# MC70_FSK_Modboard.net
KiCad netlist of a schematic drawn in EAGLE
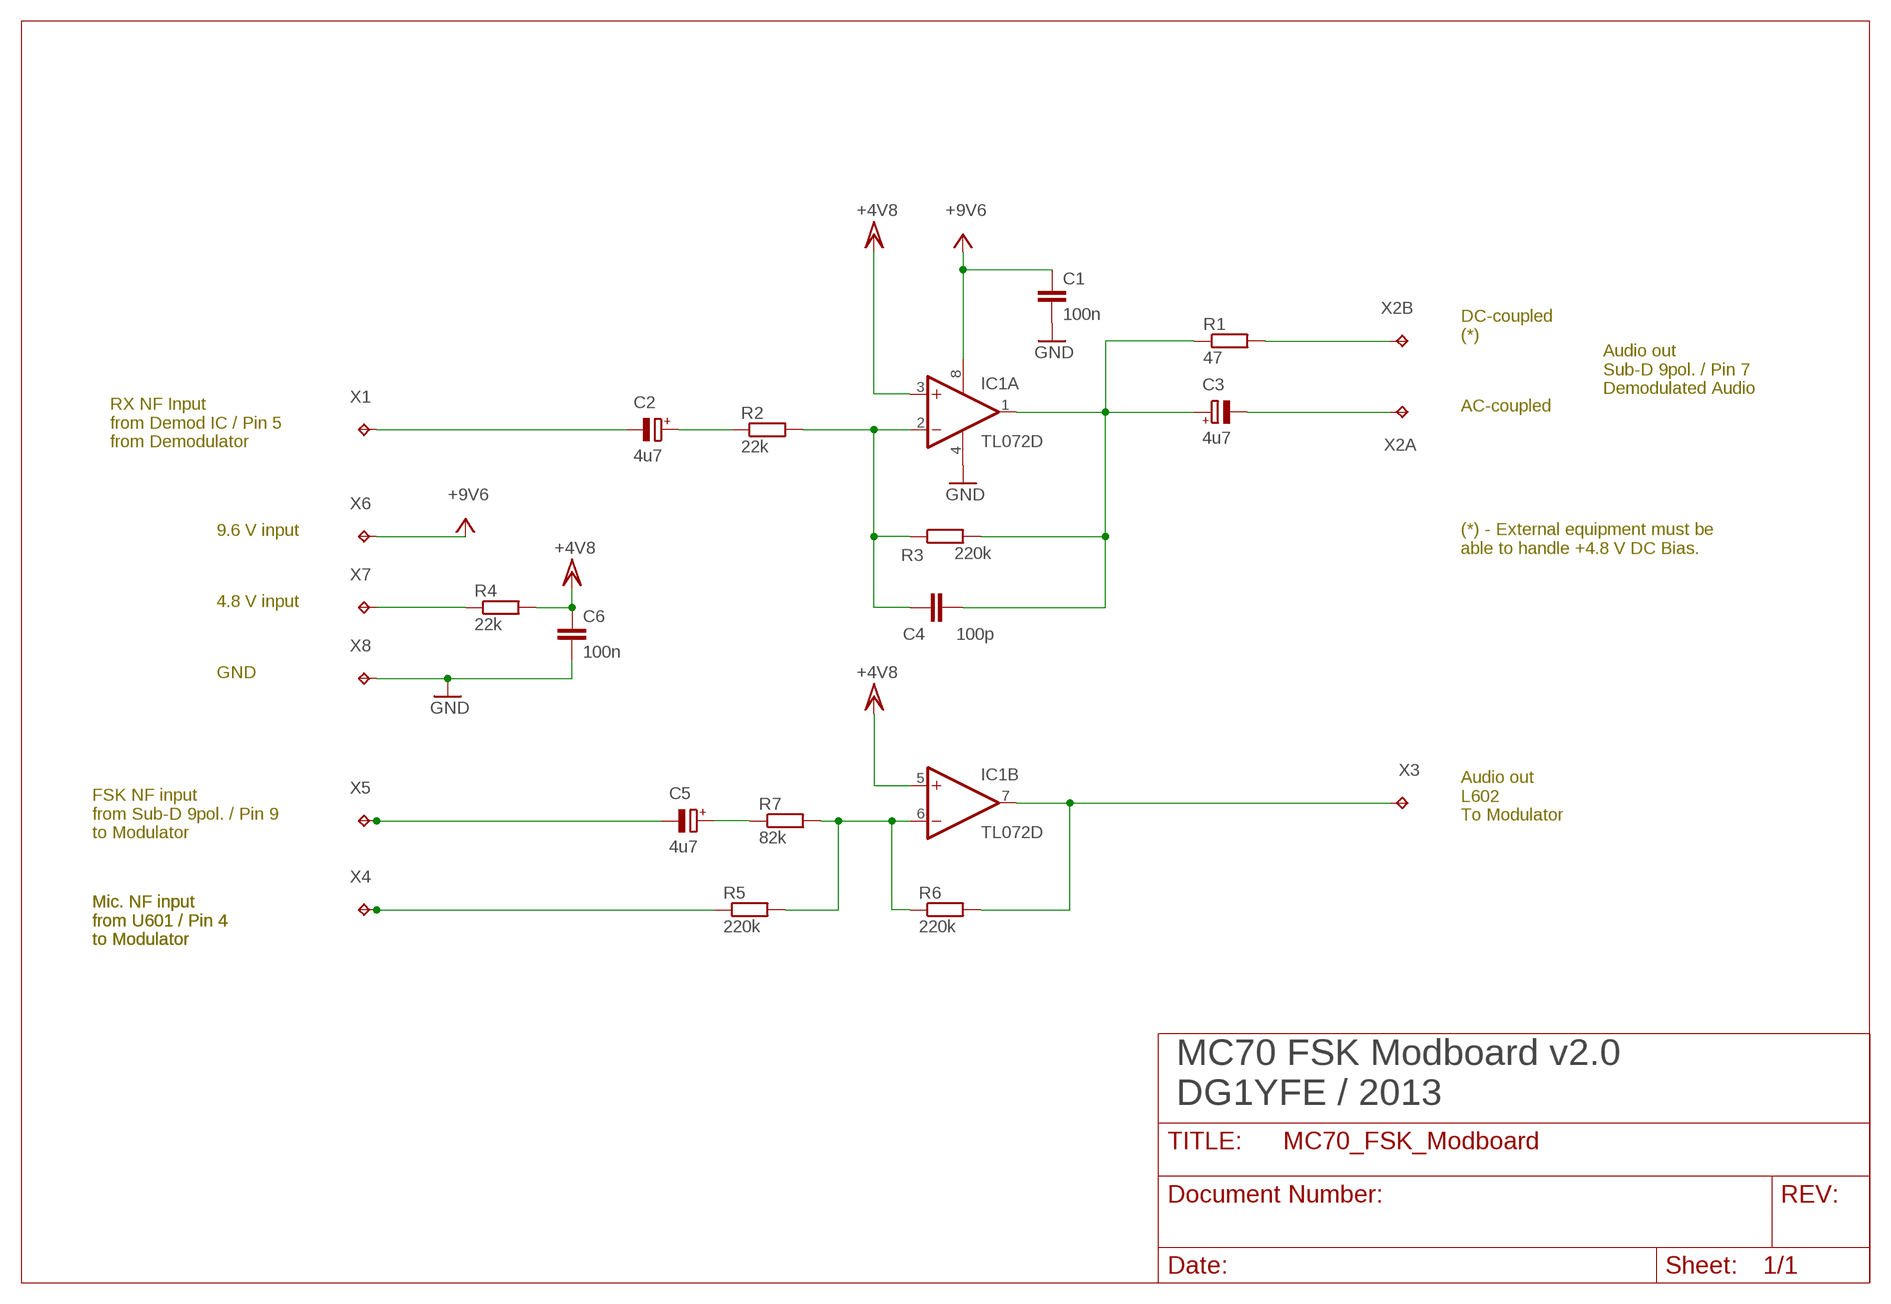
[diagram p0: schematic, sheet 1]

(export (version "E")
  (design (tool "Eeschema 10.0.6"))
  (components
    (comp (ref "C1")
      (value "100n")
      (footprint "eagle-import:C0805")
      (libsource (lib "eagle-import") (part "C-EUC0805"))
    )
    (comp (ref "C2")
      (value "4u7")
      (footprint "eagle-import:A_3216-18R")
      (libsource (lib "eagle-import") (part "CPOL-EUA/3216-18R"))
    )
    (comp (ref "C3")
      (value "4u7")
      (footprint "eagle-import:A_3216-18R")
      (libsource (lib "eagle-import") (part "CPOL-EUA/3216-18R"))
    )
    (comp (ref "C4")
      (value "100p")
      (footprint "eagle-import:C0805")
      (libsource (lib "eagle-import") (part "C-EUC0805"))
    )
    (comp (ref "C5")
      (value "4u7")
      (footprint "eagle-import:A_3216-18R")
      (libsource (lib "eagle-import") (part "CPOL-EUA/3216-18R"))
    )
    (comp (ref "C6")
      (value "100n")
      (footprint "eagle-import:C0805")
      (libsource (lib "eagle-import") (part "C-EUC0805"))
    )
    (comp (ref "IC1")
      (value "TL072D")
      (footprint "eagle-import:SO08")
      (libsource (lib "eagle-import") (part "TL072D"))
    )
    (comp (ref "R1")
      (value "47")
      (footprint "eagle-import:R0805")
      (libsource (lib "eagle-import") (part "R-EU_R0805"))
    )
    (comp (ref "R2")
      (value "22k")
      (footprint "eagle-import:R0805")
      (libsource (lib "eagle-import") (part "R-EU_R0805"))
    )
    (comp (ref "R3")
      (value "220k")
      (footprint "eagle-import:R0805")
      (libsource (lib "eagle-import") (part "R-EU_R0805"))
    )
    (comp (ref "R4")
      (value "22k")
      (footprint "eagle-import:R0805")
      (libsource (lib "eagle-import") (part "R-EU_R0805"))
    )
    (comp (ref "R5")
      (value "220k")
      (footprint "eagle-import:R0805")
      (libsource (lib "eagle-import") (part "R-EU_R0805"))
    )
    (comp (ref "R6")
      (value "220k")
      (footprint "eagle-import:R0805")
      (libsource (lib "eagle-import") (part "R-EU_R0805"))
    )
    (comp (ref "R7")
      (value "82k")
      (footprint "eagle-import:R0805")
      (libsource (lib "eagle-import") (part "R-EU_R0805"))
    )
    (comp (ref "X1")
      (value "TPTP15R")
      (footprint "eagle-import:TP15R")
      (libsource (lib "eagle-import") (part "TPTP15R"))
    )
    (comp (ref "X2A")
      (value "TPTP15R")
      (footprint "eagle-import:TP15R")
      (libsource (lib "eagle-import") (part "TPTP15R"))
    )
    (comp (ref "X2B")
      (value "TPTP15R")
      (footprint "eagle-import:TP15R")
      (libsource (lib "eagle-import") (part "TPTP15R"))
    )
    (comp (ref "X3")
      (value "TPTP15R")
      (footprint "eagle-import:TP15R")
      (libsource (lib "eagle-import") (part "TPTP15R"))
    )
    (comp (ref "X4")
      (value "TPTP15R")
      (footprint "eagle-import:TP15R")
      (libsource (lib "eagle-import") (part "TPTP15R"))
    )
    (comp (ref "X5")
      (value "TPTP15R")
      (footprint "eagle-import:TP15R")
      (libsource (lib "eagle-import") (part "TPTP15R"))
    )
    (comp (ref "X6")
      (value "TPTP15R")
      (footprint "eagle-import:TP15R")
      (libsource (lib "eagle-import") (part "TPTP15R"))
    )
    (comp (ref "X7")
      (value "TPTP15R")
      (footprint "eagle-import:TP15R")
      (libsource (lib "eagle-import") (part "TPTP15R"))
    )
    (comp (ref "X8")
      (value "TPTP15R")
      (footprint "eagle-import:TP15R")
      (libsource (lib "eagle-import") (part "TPTP15R"))
    )
  )
  (nets
    (net (code "1") (name "+4V8") (class "Default")
      (node (ref "C6") (pin "1") (pinfunction "1_1") (pintype "passive"))
      (node (ref "IC1") (pin "3") (pinfunction "+IN_3") (pintype "input"))
      (node (ref "IC1") (pin "5") (pinfunction "+IN_5") (pintype "input"))
      (node (ref "R4") (pin "2") (pinfunction "2_2") (pintype "passive"))
    )
    (net (code "2") (name "+9V6") (class "Default")
      (node (ref "C1") (pin "1") (pinfunction "1_1") (pintype "passive"))
      (node (ref "IC1") (pin "8") (pinfunction "V+_8") (pintype "power_in"))
      (node (ref "X6") (pin "TP") (pinfunction "TP_TP") (pintype "input"))
    )
    (net (code "3") (name "GND") (class "Default")
      (node (ref "C1") (pin "2") (pinfunction "2_2") (pintype "passive"))
      (node (ref "C6") (pin "2") (pinfunction "2_2") (pintype "passive"))
      (node (ref "IC1") (pin "4") (pinfunction "V-_4") (pintype "power_in"))
      (node (ref "X8") (pin "TP") (pinfunction "TP_TP") (pintype "input"))
    )
    (net (code "4") (name "Net-(C2-Pad+)") (class "Default")
      (node (ref "C2") (pin "+") (pinfunction "+_+") (pintype "passive"))
      (node (ref "R2") (pin "1") (pinfunction "1_1") (pintype "passive"))
    )
    (net (code "5") (name "Net-(C2-Pad-)") (class "Default")
      (node (ref "C2") (pin "-") (pinfunction "-_-") (pintype "passive"))
      (node (ref "X1") (pin "TP") (pinfunction "TP_TP") (pintype "input"))
    )
    (net (code "6") (name "Net-(C3-Pad-)") (class "Default")
      (node (ref "C3") (pin "-") (pinfunction "-_-") (pintype "passive"))
      (node (ref "X2A") (pin "TP") (pinfunction "TP_TP") (pintype "input"))
    )
    (net (code "7") (name "Net-(C5-Pad+)") (class "Default")
      (node (ref "C5") (pin "+") (pinfunction "+_+") (pintype "passive"))
      (node (ref "R7") (pin "1") (pinfunction "1_1") (pintype "passive"))
    )
    (net (code "8") (name "Net-(C5-Pad-)") (class "Default")
      (node (ref "C5") (pin "-") (pinfunction "-_-") (pintype "passive"))
      (node (ref "X5") (pin "TP") (pinfunction "TP_TP") (pintype "input"))
    )
    (net (code "9") (name "Net-(IC1A--IN)") (class "Default")
      (node (ref "C4") (pin "2") (pinfunction "2_2") (pintype "passive"))
      (node (ref "IC1") (pin "2") (pinfunction "-IN_2") (pintype "input"))
      (node (ref "R2") (pin "2") (pinfunction "2_2") (pintype "passive"))
      (node (ref "R3") (pin "1") (pinfunction "1_1") (pintype "passive"))
    )
    (net (code "10") (name "Net-(IC1A-OUT)") (class "Default")
      (node (ref "C3") (pin "+") (pinfunction "+_+") (pintype "passive"))
      (node (ref "C4") (pin "1") (pinfunction "1_1") (pintype "passive"))
      (node (ref "IC1") (pin "1") (pinfunction "OUT_1") (pintype "output"))
      (node (ref "R1") (pin "1") (pinfunction "1_1") (pintype "passive"))
      (node (ref "R3") (pin "2") (pinfunction "2_2") (pintype "passive"))
    )
    (net (code "11") (name "Net-(IC1B--IN)") (class "Default")
      (node (ref "IC1") (pin "6") (pinfunction "-IN_6") (pintype "input"))
      (node (ref "R5") (pin "2") (pinfunction "2_2") (pintype "passive"))
      (node (ref "R6") (pin "1") (pinfunction "1_1") (pintype "passive"))
      (node (ref "R7") (pin "2") (pinfunction "2_2") (pintype "passive"))
    )
    (net (code "12") (name "Net-(IC1B-OUT)") (class "Default")
      (node (ref "IC1") (pin "7") (pinfunction "OUT_7") (pintype "output"))
      (node (ref "R6") (pin "2") (pinfunction "2_2") (pintype "passive"))
      (node (ref "X3") (pin "TP") (pinfunction "TP_TP") (pintype "input"))
    )
    (net (code "13") (name "Net-(R1-Pad2)") (class "Default")
      (node (ref "R1") (pin "2") (pinfunction "2_2") (pintype "passive"))
      (node (ref "X2B") (pin "TP") (pinfunction "TP_TP") (pintype "input"))
    )
    (net (code "14") (name "Net-(R4-Pad1)") (class "Default")
      (node (ref "R4") (pin "1") (pinfunction "1_1") (pintype "passive"))
      (node (ref "X7") (pin "TP") (pinfunction "TP_TP") (pintype "input"))
    )
    (net (code "15") (name "Net-(R5-Pad1)") (class "Default")
      (node (ref "R5") (pin "1") (pinfunction "1_1") (pintype "passive"))
      (node (ref "X4") (pin "TP") (pinfunction "TP_TP") (pintype "input"))
    )
  )
)
